# Power_Management.net
KiCad netlist of a schematic drawn in EAGLE
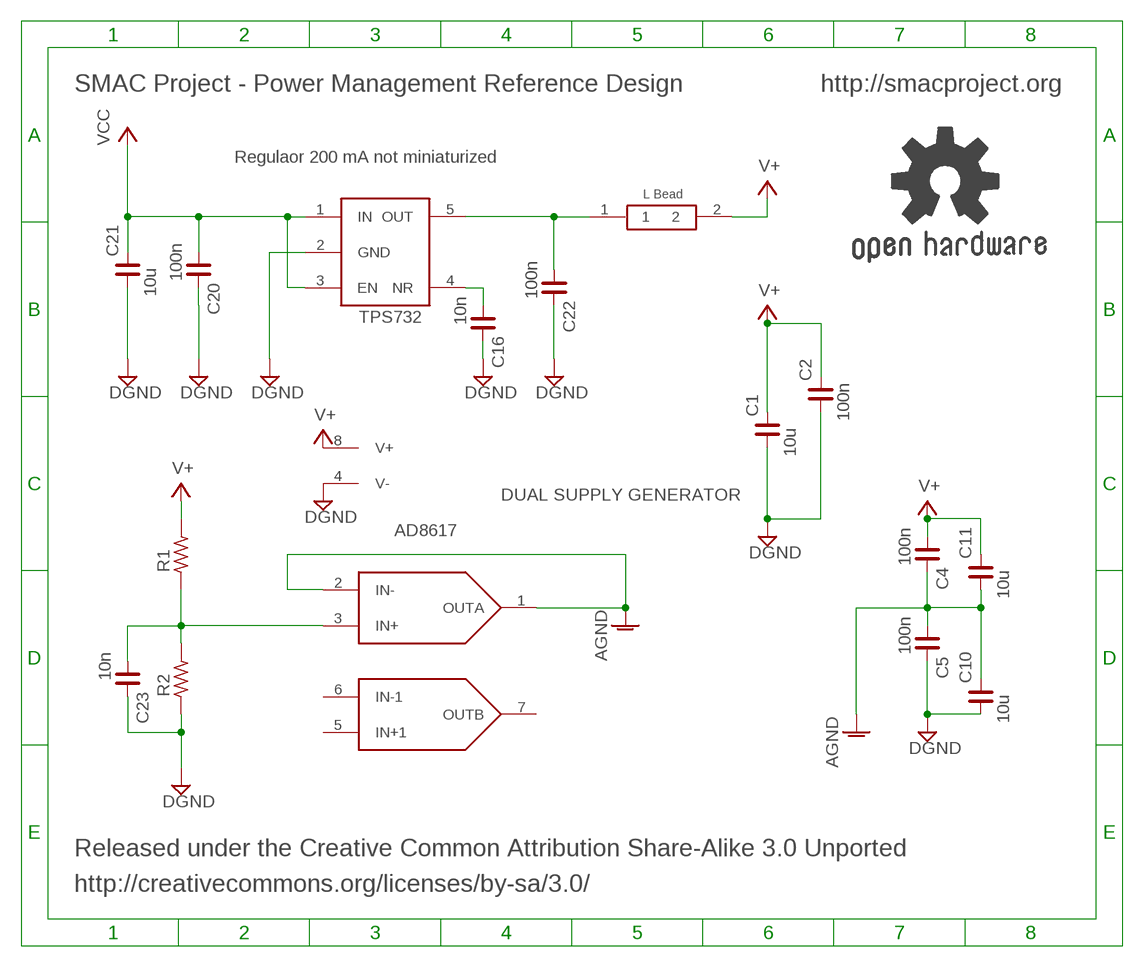
[diagram p0: schematic, sheet 1]

(export (version "E")
  (design (tool "Eeschema 10.0.6"))
  (components
    (comp (ref "C1")
      (value "10u")
      (footprint "eagle-import:C0402")
      (libsource (lib "eagle-import") (part "C_0402"))
    )
    (comp (ref "C2")
      (value "100n")
      (footprint "eagle-import:C0402")
      (libsource (lib "eagle-import") (part "C_0402"))
    )
    (comp (ref "C4")
      (value "100n")
      (footprint "eagle-import:C0402")
      (libsource (lib "eagle-import") (part "C_0402"))
    )
    (comp (ref "C5")
      (value "100n")
      (footprint "eagle-import:C0402")
      (libsource (lib "eagle-import") (part "C_0402"))
    )
    (comp (ref "C10")
      (value "10u")
      (footprint "eagle-import:C0402")
      (libsource (lib "eagle-import") (part "C_0402"))
    )
    (comp (ref "C11")
      (value "10u")
      (footprint "eagle-import:C0402")
      (libsource (lib "eagle-import") (part "C_0402"))
    )
    (comp (ref "C16")
      (value "10n")
      (footprint "eagle-import:C0402")
      (libsource (lib "eagle-import") (part "C_0402"))
    )
    (comp (ref "C20")
      (value "100n")
      (footprint "eagle-import:C0402")
      (libsource (lib "eagle-import") (part "C_0402"))
    )
    (comp (ref "C21")
      (value "10u")
      (footprint "eagle-import:C0402")
      (libsource (lib "eagle-import") (part "C_0402"))
    )
    (comp (ref "C22")
      (value "100n")
      (footprint "eagle-import:C0402")
      (libsource (lib "eagle-import") (part "C_0402"))
    )
    (comp (ref "C23")
      (value "10n")
      (footprint "eagle-import:C0402")
      (libsource (lib "eagle-import") (part "C_0402"))
    )
    (comp (ref "GOLD_ORB_SM1")
      (value "OSHWLOGO_REF_SM")
      (footprint "eagle-import:OSHW2REF")
      (libsource (lib "eagle-import") (part "OSHWLOGO_REF_SM"))
    )
    (comp (ref "IC1")
      (value "TPS732XX")
      (footprint "eagle-import:SOT23")
      (libsource (lib "eagle-import") (part "TPS732XX"))
    )
    (comp (ref "IC2")
      (value "AD8617")
      (footprint "eagle-import:MSOP8")
      (libsource (lib "eagle-import") (part "AD8617"))
    )
    (comp (ref "L-BEAD")
      (value "L-BEAD")
      (footprint "eagle-import:0402")
      (libsource (lib "eagle-import") (part "L-BEAD"))
    )
    (comp (ref "R1")
      (value "R_0402")
      (footprint "eagle-import:R0402")
      (libsource (lib "eagle-import") (part "R_0402"))
    )
    (comp (ref "R2")
      (value "R_0402")
      (footprint "eagle-import:R0402")
      (libsource (lib "eagle-import") (part "R_0402"))
    )
  )
  (nets
    (net (code "1") (name "AGND") (class "Default")
      (node (ref "C10") (pin "2") (pinfunction "2_2") (pintype "passive"))
      (node (ref "C11") (pin "1") (pinfunction "1_1") (pintype "passive"))
      (node (ref "C4") (pin "2") (pinfunction "2_2") (pintype "passive"))
      (node (ref "C5") (pin "1") (pinfunction "1_1") (pintype "passive"))
      (node (ref "IC2") (pin "1") (pinfunction "OUTA_1") (pintype "bidirectional"))
      (node (ref "IC2") (pin "2") (pinfunction "IN-_2") (pintype "bidirectional"))
    )
    (net (code "2") (name "DGND") (class "Default")
      (node (ref "C1") (pin "1") (pinfunction "1_1") (pintype "passive"))
      (node (ref "C10") (pin "1") (pinfunction "1_1") (pintype "passive"))
      (node (ref "C16") (pin "2") (pinfunction "2_2") (pintype "passive"))
      (node (ref "C2") (pin "1") (pinfunction "1_1") (pintype "passive"))
      (node (ref "C20") (pin "2") (pinfunction "2_2") (pintype "passive"))
      (node (ref "C21") (pin "1") (pinfunction "1_1") (pintype "passive"))
      (node (ref "C22") (pin "2") (pinfunction "2_2") (pintype "passive"))
      (node (ref "C23") (pin "2") (pinfunction "2_2") (pintype "passive"))
      (node (ref "C5") (pin "2") (pinfunction "2_2") (pintype "passive"))
      (node (ref "IC1") (pin "2") (pinfunction "GND_2") (pintype "bidirectional"))
      (node (ref "IC2") (pin "4") (pinfunction "V-_4") (pintype "bidirectional"))
      (node (ref "R2") (pin "1") (pinfunction "1_1") (pintype "passive"))
    )
    (net (code "3") (name "Net-(IC1-NR)") (class "Default")
      (node (ref "C16") (pin "1") (pinfunction "1_1") (pintype "passive"))
      (node (ref "IC1") (pin "4") (pinfunction "NR_4") (pintype "bidirectional"))
    )
    (net (code "4") (name "Net-(IC1-OUT)") (class "Default")
      (node (ref "C22") (pin "1") (pinfunction "1_1") (pintype "passive"))
      (node (ref "IC1") (pin "5") (pinfunction "OUT_5") (pintype "bidirectional"))
      (node (ref "L-BEAD") (pin "1") (pinfunction "1_1") (pintype "bidirectional"))
    )
    (net (code "5") (name "Net-(IC2-IN+)") (class "Default")
      (node (ref "C23") (pin "1") (pinfunction "1_1") (pintype "passive"))
      (node (ref "IC2") (pin "3") (pinfunction "IN+_3") (pintype "bidirectional"))
      (node (ref "R1") (pin "1") (pinfunction "1_1") (pintype "passive"))
      (node (ref "R2") (pin "2") (pinfunction "2_2") (pintype "passive"))
    )
    (net (code "6") (name "V+") (class "Default")
      (node (ref "C1") (pin "2") (pinfunction "2_2") (pintype "passive"))
      (node (ref "C11") (pin "2") (pinfunction "2_2") (pintype "passive"))
      (node (ref "C2") (pin "2") (pinfunction "2_2") (pintype "passive"))
      (node (ref "C4") (pin "1") (pinfunction "1_1") (pintype "passive"))
      (node (ref "IC2") (pin "8") (pinfunction "V+_8") (pintype "bidirectional"))
      (node (ref "L-BEAD") (pin "2") (pinfunction "2_2") (pintype "bidirectional"))
      (node (ref "R1") (pin "2") (pinfunction "2_2") (pintype "passive"))
    )
    (net (code "7") (name "VCC") (class "Default")
      (node (ref "C20") (pin "1") (pinfunction "1_1") (pintype "passive"))
      (node (ref "C21") (pin "2") (pinfunction "2_2") (pintype "passive"))
      (node (ref "IC1") (pin "1") (pinfunction "IN_1") (pintype "bidirectional"))
      (node (ref "IC1") (pin "3") (pinfunction "EN_3") (pintype "bidirectional"))
    )
    (net (code "8") (name "unconnected-(IC2-IN+1-Pad5)") (class "Default")
      (node (ref "IC2") (pin "5") (pinfunction "IN+1_5") (pintype "bidirectional"))
    )
    (net (code "9") (name "unconnected-(IC2-IN-1-Pad6)") (class "Default")
      (node (ref "IC2") (pin "6") (pinfunction "IN-1_6") (pintype "bidirectional"))
    )
    (net (code "10") (name "unconnected-(IC2-OUTB-Pad7)") (class "Default")
      (node (ref "IC2") (pin "7") (pinfunction "OUTB_7") (pintype "bidirectional"))
    )
  )
)
